# SCHEMATICS.net
KiCad netlist of a schematic drawn in EasyEDA
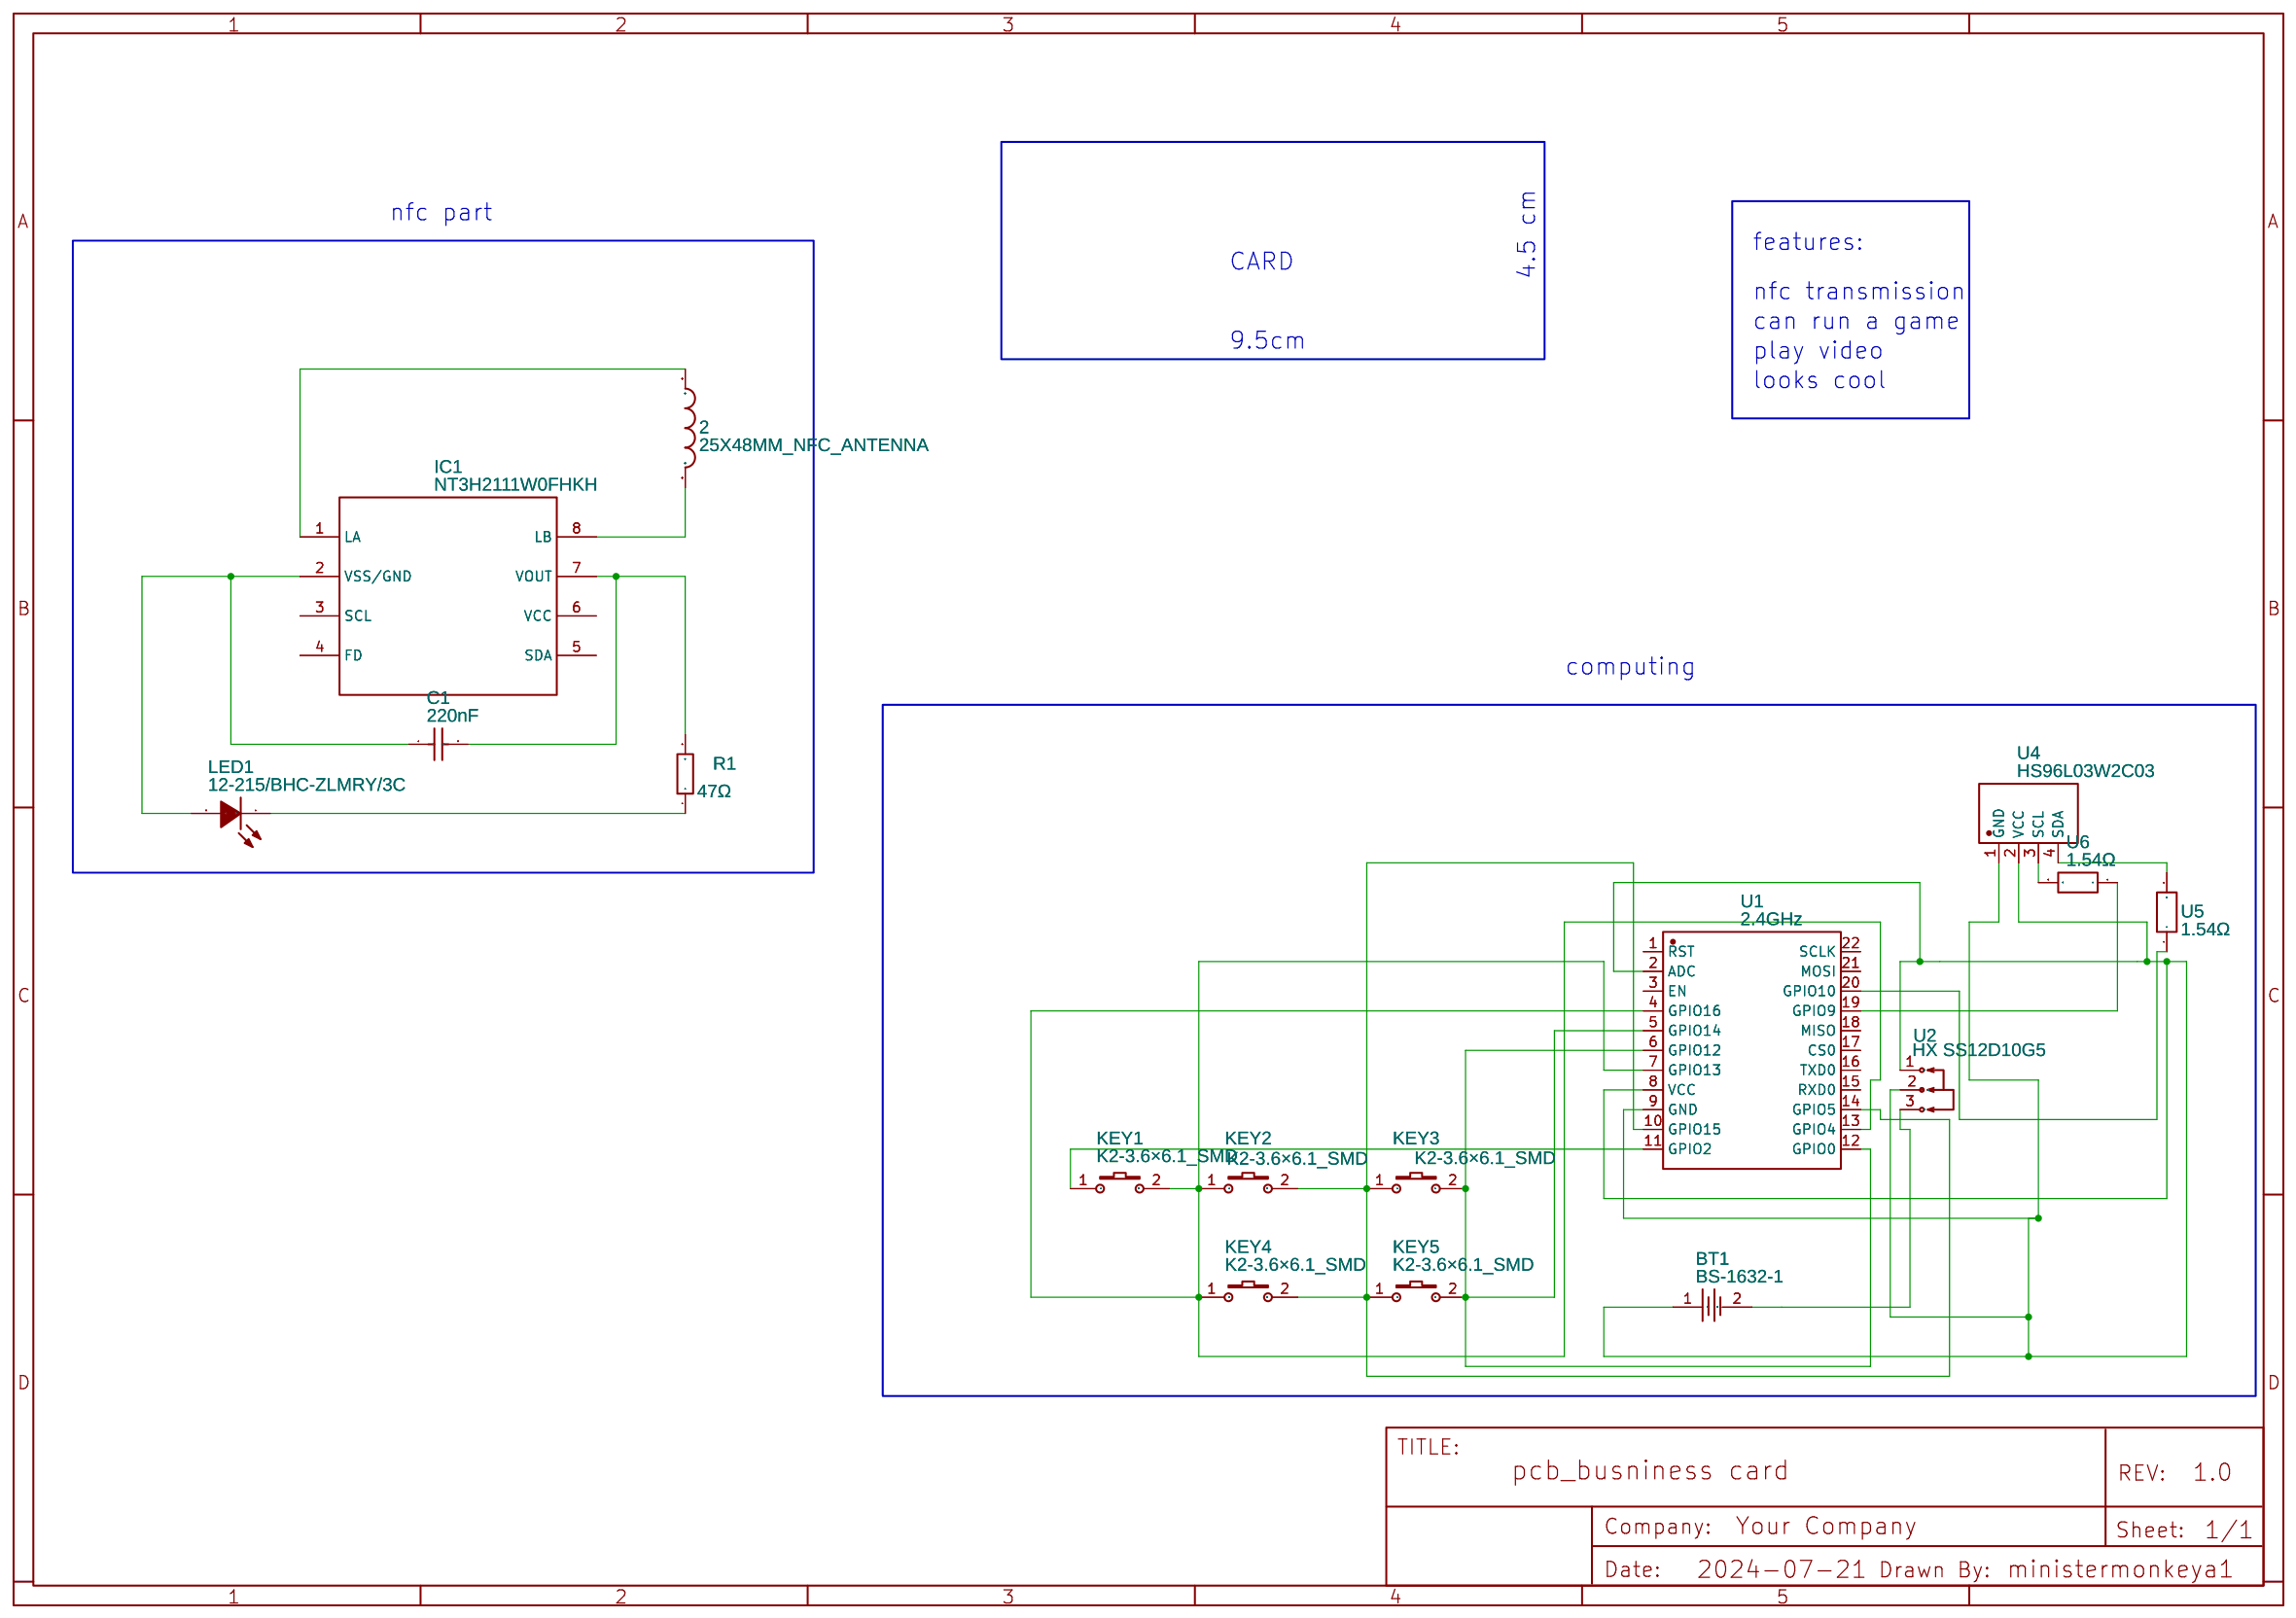
[diagram p0: schem1]
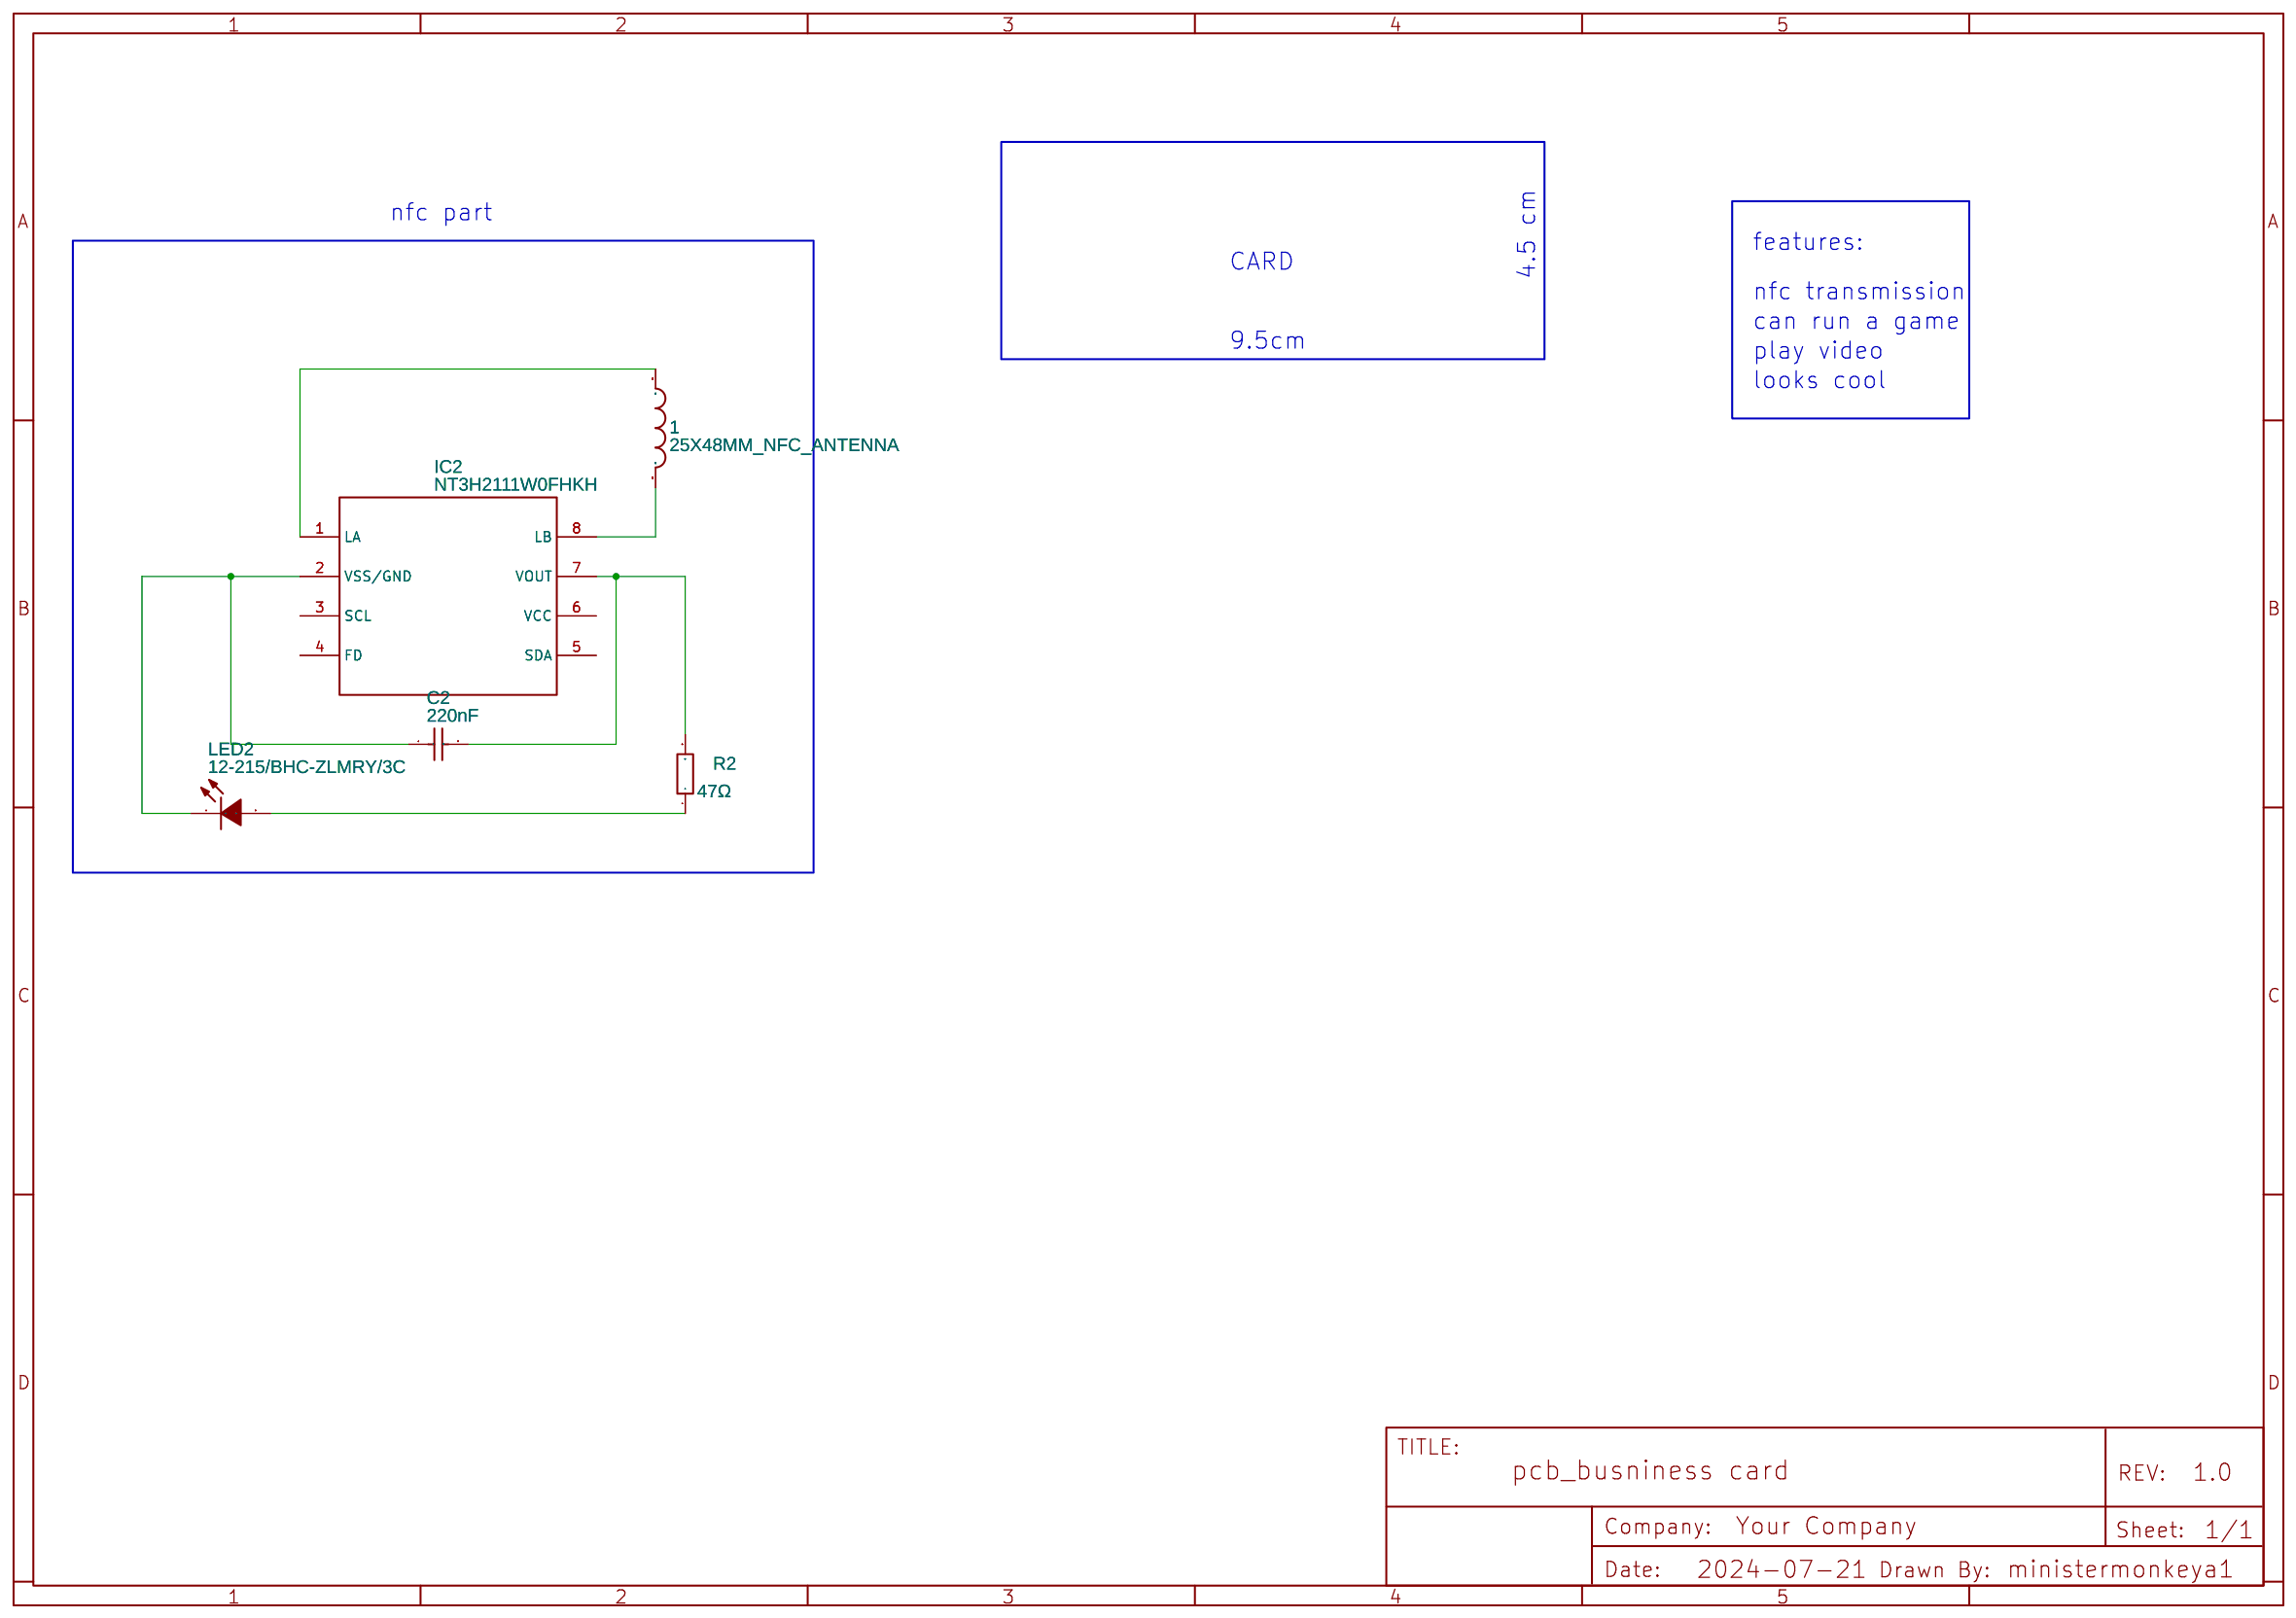
[diagram p1: schem1 copy]

(export (version "E")
  (design (tool "Eeschema 10.0.6"))
  (components
    (comp (ref "2") (value "25X48MM_NFC_ANTENNA") (libsource (lib "") (part "25X48MM_NFC_ANTENNA")))
    (comp (ref "BT1")
      (value "BS-1632-1")
      (fields (field (name "Manufacturer") "Q&J"))
      (libsource (lib "") (part "BS-1632-1"))
    )
    (comp (ref "C1")
      (value "220nF")
      (fields (field (name "Manufacturer Part") "C2012X7R1E224KT0H0N") (field (name "Manufacturer") "TDK"))
      (libsource (lib "") (part "C2012X7R1E224KT0H0N"))
    )
    (comp (ref "IC1")
      (value "NT3H2111W0FHKH")
      (fields (field (name "Manufacturer") "NXP(恩智浦)"))
      (libsource (lib "") (part "NT3H2111W0FHKH"))
    )
    (comp (ref "KEY1")
      (value "K2-3.6×6.1_SMD")
      (fields (field (name "Manufacturer Part") "K2-1107ST-A4SW-06"))
      (libsource (lib "") (part "K2-3.6×6.1_SMD"))
    )
    (comp (ref "KEY2")
      (value "K2-3.6×6.1_SMD")
      (fields (field (name "Manufacturer Part") "K2-1107ST-A4SW-06"))
      (libsource (lib "") (part "K2-3.6×6.1_SMD"))
    )
    (comp (ref "KEY3")
      (value "K2-3.6×6.1_SMD")
      (fields (field (name "Manufacturer Part") "K2-1107ST-A4SW-06"))
      (libsource (lib "") (part "K2-3.6×6.1_SMD"))
    )
    (comp (ref "KEY4")
      (value "K2-3.6×6.1_SMD")
      (fields (field (name "Manufacturer Part") "K2-1107ST-A4SW-06"))
      (libsource (lib "") (part "K2-3.6×6.1_SMD"))
    )
    (comp (ref "KEY5")
      (value "K2-3.6×6.1_SMD")
      (fields (field (name "Manufacturer Part") "K2-1107ST-A4SW-06"))
      (libsource (lib "") (part "K2-3.6×6.1_SMD"))
    )
    (comp (ref "LED1")
      (value "12-215/BHC-ZLMRY/3C")
      (fields (field (name "Manufacturer") "EVERLIGHT(亿光)"))
      (libsource (lib "") (part "12-215/BHC-ZLMRY/3C"))
    )
    (comp (ref "R1")
      (value "47Ω")
      (fields
        (field (name "Manufacturer Part") "0603WAF470JT5E")
        (field (name "Manufacturer") "UNI-ROYAL(厚声)")
      )
      (libsource (lib "") (part "0603WAF470JT5E"))
    )
    (comp (ref "U1")
      (value "2.4GHz")
      (fields
        (field (name "Manufacturer Part") "ESP-12F(ESP8266MOD)")
        (field (name "Manufacturer") "Ai-Thinker(安信可)")
      )
      (libsource (lib "") (part "ESP-12F(ESP8266MOD)"))
    )
    (comp (ref "U2")
      (value "HX SS12D10G5")
      (fields (field (name "Manufacturer") "hanxia(韩下)"))
      (libsource (lib "") (part "HX SS12D10G5"))
    )
    (comp (ref "U4")
      (value "HS96L03W2C03")
      (fields (field (name "Manufacturer") "HS(汉昇)"))
      (libsource (lib "") (part "HS96L03W2C03"))
    )
    (comp (ref "U5")
      (value "1.54Ω")
      (fields (field (name "Manufacturer Part") "MF0204FRE52-1R54") (field (name "Manufacturer") "YAGEO(国巨)"))
      (libsource (lib "") (part "MF0204FRE52-1R54"))
    )
    (comp (ref "U6")
      (value "1.54Ω")
      (fields (field (name "Manufacturer Part") "MF0204FRE52-1R54") (field (name "Manufacturer") "YAGEO(国巨)"))
      (libsource (lib "") (part "MF0204FRE52-1R54_1"))
    )
    (comp (ref "1") (value "25X48MM_NFC_ANTENNA") (libsource (lib "") (part "25X48MM_NFC_ANTENNA")))
    (comp (ref "C2")
      (value "220nF")
      (fields (field (name "Manufacturer Part") "C2012X7R1E224KT0H0N") (field (name "Manufacturer") "TDK"))
      (libsource (lib "") (part "C2012X7R1E224KT0H0N"))
    )
    (comp (ref "IC2")
      (value "NT3H2111W0FHKH")
      (fields (field (name "Manufacturer") "NXP(恩智浦)"))
      (libsource (lib "") (part "NT3H2111W0FHKH"))
    )
    (comp (ref "LED2")
      (value "12-215/BHC-ZLMRY/3C")
      (fields (field (name "Manufacturer") "EVERLIGHT(亿光)"))
      (libsource (lib "") (part "12-215/BHC-ZLMRY/3C"))
    )
    (comp (ref "R2")
      (value "47Ω")
      (fields
        (field (name "Manufacturer Part") "0603WAF470JT5E")
        (field (name "Manufacturer") "UNI-ROYAL(厚声)")
      )
      (libsource (lib "") (part "0603WAF470JT5E"))
    )
  )
  (nets
    (net (code "1") (name "Net-(BT1-Pad2)") (class "Default")
      (node (ref "BT1") (pin "2") (pinfunction "2_2") (pintype "input"))
      (node (ref "U2") (pin "3") (pinfunction "3_3") (pintype "unspecified"))
    )
    (net (code "2") (name "Net-(IC1-LA)") (class "Default")
      (node (ref "2") (pin "P$1") (pinfunction "P$1_P$1") (pintype "bidirectional"))
      (node (ref "IC1") (pin "1") (pinfunction "LA_1") (pintype "unspecified"))
    )
    (net (code "3") (name "Net-(IC1-LB)") (class "Default")
      (node (ref "2") (pin "P$2") (pinfunction "P$2_P$2") (pintype "bidirectional"))
      (node (ref "IC1") (pin "8") (pinfunction "LB_8") (pintype "unspecified"))
    )
    (net (code "4") (name "Net-(IC1-VOUT)") (class "Default")
      (node (ref "C1") (pin "2") (pinfunction "2_2") (pintype "input"))
      (node (ref "IC1") (pin "7") (pinfunction "VOUT_7") (pintype "passive"))
      (node (ref "R1") (pin "2") (pinfunction "2_2") (pintype "input"))
    )
    (net (code "5") (name "Net-(IC1-VSS{slash}GND)") (class "Default")
      (node (ref "C1") (pin "1") (pinfunction "1_1") (pintype "input"))
      (node (ref "IC1") (pin "2") (pinfunction "VSS/GND_2") (pintype "unspecified"))
      (node (ref "LED1") (pin "2") (pinfunction "A_2") (pintype "unspecified"))
    )
    (net (code "6") (name "Net-(IC2-LA)") (class "Default")
      (node (ref "1") (pin "P$1") (pinfunction "P$1_P$1") (pintype "bidirectional"))
      (node (ref "IC2") (pin "1") (pinfunction "LA_1") (pintype "unspecified"))
    )
    (net (code "7") (name "Net-(IC2-LB)") (class "Default")
      (node (ref "1") (pin "P$2") (pinfunction "P$2_P$2") (pintype "bidirectional"))
      (node (ref "IC2") (pin "8") (pinfunction "LB_8") (pintype "unspecified"))
    )
    (net (code "8") (name "Net-(IC2-VOUT)") (class "Default")
      (node (ref "C2") (pin "2") (pinfunction "2_2") (pintype "input"))
      (node (ref "IC2") (pin "7") (pinfunction "VOUT_7") (pintype "passive"))
      (node (ref "R2") (pin "2") (pinfunction "2_2") (pintype "input"))
    )
    (net (code "9") (name "Net-(IC2-VSS{slash}GND)") (class "Default")
      (node (ref "C2") (pin "1") (pinfunction "1_1") (pintype "input"))
      (node (ref "IC2") (pin "2") (pinfunction "VSS/GND_2") (pintype "unspecified"))
      (node (ref "LED2") (pin "1") (pinfunction "K_1") (pintype "unspecified"))
    )
    (net (code "10") (name "Net-(LED1-K)") (class "Default")
      (node (ref "LED1") (pin "1") (pinfunction "K_1") (pintype "unspecified"))
      (node (ref "R1") (pin "1") (pinfunction "1_1") (pintype "input"))
    )
    (net (code "11") (name "Net-(LED2-A)") (class "Default")
      (node (ref "LED2") (pin "2") (pinfunction "A_2") (pintype "unspecified"))
      (node (ref "R2") (pin "1") (pinfunction "1_1") (pintype "input"))
    )
    (net (code "12") (name "Net-(U1-ADC)") (class "Default")
      (node (ref "BT1") (pin "1") (pinfunction "1_1") (pintype "input"))
      (node (ref "U1") (pin "2") (pinfunction "ADC_2") (pintype "unspecified"))
      (node (ref "U1") (pin "8") (pinfunction "VCC_8") (pintype "unspecified"))
      (node (ref "U1") (pin "9") (pinfunction "GND_9") (pintype "unspecified"))
      (node (ref "U2") (pin "1") (pinfunction "1_1") (pintype "unspecified"))
      (node (ref "U2") (pin "2") (pinfunction "2_2") (pintype "unspecified"))
      (node (ref "U4") (pin "1") (pinfunction "GND_1") (pintype "unspecified"))
      (node (ref "U4") (pin "2") (pinfunction "VCC_2") (pintype "unspecified"))
    )
    (net (code "13") (name "Net-(U1-GPIO0)") (class "Default")
      (node (ref "KEY3") (pin "2") (pinfunction "2_2") (pintype "unspecified"))
      (node (ref "KEY5") (pin "2") (pinfunction "2_2") (pintype "unspecified"))
      (node (ref "U1") (pin "12") (pinfunction "GPIO0_12") (pintype "unspecified"))
      (node (ref "U1") (pin "5") (pinfunction "GPIO14_5") (pintype "unspecified"))
      (node (ref "U1") (pin "6") (pinfunction "GPIO12_6") (pintype "unspecified"))
    )
    (net (code "14") (name "Net-(U1-GPIO2)") (class "Default")
      (node (ref "KEY1") (pin "1") (pinfunction "1_1") (pintype "unspecified"))
      (node (ref "U1") (pin "11") (pinfunction "GPIO2_11") (pintype "unspecified"))
    )
    (net (code "15") (name "Net-(U1-GPIO9)") (class "Default")
      (node (ref "U1") (pin "19") (pinfunction "GPIO9_19") (pintype "unspecified"))
      (node (ref "U6") (pin "1") (pinfunction "1_1") (pintype "unspecified"))
    )
    (net (code "16") (name "Net-(U1-GPIO10)") (class "Default")
      (node (ref "U1") (pin "20") (pinfunction "GPIO10_20") (pintype "unspecified"))
      (node (ref "U5") (pin "1") (pinfunction "1_1") (pintype "unspecified"))
    )
    (net (code "17") (name "Net-(U1-GPIO13)") (class "Default")
      (node (ref "KEY1") (pin "2") (pinfunction "2_2") (pintype "unspecified"))
      (node (ref "KEY2") (pin "1") (pinfunction "1_1") (pintype "unspecified"))
      (node (ref "KEY4") (pin "1") (pinfunction "1_1") (pintype "unspecified"))
      (node (ref "U1") (pin "13") (pinfunction "GPIO4_13") (pintype "unspecified"))
      (node (ref "U1") (pin "4") (pinfunction "GPIO16_4") (pintype "unspecified"))
      (node (ref "U1") (pin "7") (pinfunction "GPIO13_7") (pintype "unspecified"))
    )
    (net (code "18") (name "Net-(U1-GPIO15)") (class "Default")
      (node (ref "KEY2") (pin "2") (pinfunction "2_2") (pintype "unspecified"))
      (node (ref "KEY3") (pin "1") (pinfunction "1_1") (pintype "unspecified"))
      (node (ref "KEY4") (pin "2") (pinfunction "2_2") (pintype "unspecified"))
      (node (ref "KEY5") (pin "1") (pinfunction "1_1") (pintype "unspecified"))
      (node (ref "U1") (pin "10") (pinfunction "GPIO15_10") (pintype "unspecified"))
      (node (ref "U1") (pin "14") (pinfunction "GPIO5_14") (pintype "unspecified"))
    )
    (net (code "19") (name "Net-(U4-SCL)") (class "Default")
      (node (ref "U4") (pin "3") (pinfunction "SCL_3") (pintype "unspecified"))
      (node (ref "U6") (pin "2") (pinfunction "2_2") (pintype "unspecified"))
    )
    (net (code "20") (name "Net-(U4-SDA)") (class "Default")
      (node (ref "U4") (pin "4") (pinfunction "SDA_4") (pintype "unspecified"))
      (node (ref "U5") (pin "2") (pinfunction "2_2") (pintype "unspecified"))
    )
    (net (code "21") (name "unconnected-(IC1-FD-Pad4)") (class "Default")
      (node (ref "IC1") (pin "4") (pinfunction "FD_4") (pintype "unspecified"))
    )
    (net (code "22") (name "unconnected-(IC1-SCL-Pad3)") (class "Default")
      (node (ref "IC1") (pin "3") (pinfunction "SCL_3") (pintype "unspecified"))
    )
    (net (code "23") (name "unconnected-(IC1-SDA-Pad5)") (class "Default")
      (node (ref "IC1") (pin "5") (pinfunction "SDA_5") (pintype "unspecified"))
    )
    (net (code "24") (name "unconnected-(IC1-VCC-Pad6)") (class "Default")
      (node (ref "IC1") (pin "6") (pinfunction "VCC_6") (pintype "passive"))
    )
    (net (code "25") (name "unconnected-(IC2-FD-Pad4)") (class "Default")
      (node (ref "IC2") (pin "4") (pinfunction "FD_4") (pintype "unspecified"))
    )
    (net (code "26") (name "unconnected-(IC2-SCL-Pad3)") (class "Default")
      (node (ref "IC2") (pin "3") (pinfunction "SCL_3") (pintype "unspecified"))
    )
    (net (code "27") (name "unconnected-(IC2-SDA-Pad5)") (class "Default")
      (node (ref "IC2") (pin "5") (pinfunction "SDA_5") (pintype "unspecified"))
    )
    (net (code "28") (name "unconnected-(IC2-VCC-Pad6)") (class "Default")
      (node (ref "IC2") (pin "6") (pinfunction "VCC_6") (pintype "passive"))
    )
    (net (code "29") (name "unconnected-(U1-CS0-Pad17)") (class "Default")
      (node (ref "U1") (pin "17") (pinfunction "CS0_17") (pintype "unspecified"))
    )
    (net (code "30") (name "unconnected-(U1-EN-Pad3)") (class "Default")
      (node (ref "U1") (pin "3") (pinfunction "EN_3") (pintype "unspecified"))
    )
    (net (code "31") (name "unconnected-(U1-MISO-Pad18)") (class "Default")
      (node (ref "U1") (pin "18") (pinfunction "MISO_18") (pintype "unspecified"))
    )
    (net (code "32") (name "unconnected-(U1-MOSI-Pad21)") (class "Default")
      (node (ref "U1") (pin "21") (pinfunction "MOSI_21") (pintype "unspecified"))
    )
    (net (code "33") (name "unconnected-(U1-RST-Pad1)") (class "Default")
      (node (ref "U1") (pin "1") (pinfunction "RST_1") (pintype "unspecified"))
    )
    (net (code "34") (name "unconnected-(U1-RXD0-Pad15)") (class "Default")
      (node (ref "U1") (pin "15") (pinfunction "RXD0_15") (pintype "unspecified"))
    )
    (net (code "35") (name "unconnected-(U1-SCLK-Pad22)") (class "Default")
      (node (ref "U1") (pin "22") (pinfunction "SCLK_22") (pintype "unspecified"))
    )
    (net (code "36") (name "unconnected-(U1-TXD0-Pad16)") (class "Default")
      (node (ref "U1") (pin "16") (pinfunction "TXD0_16") (pintype "unspecified"))
    )
  )
)
